# HDD.net
KiCad netlist of a schematic drawn in EAGLE
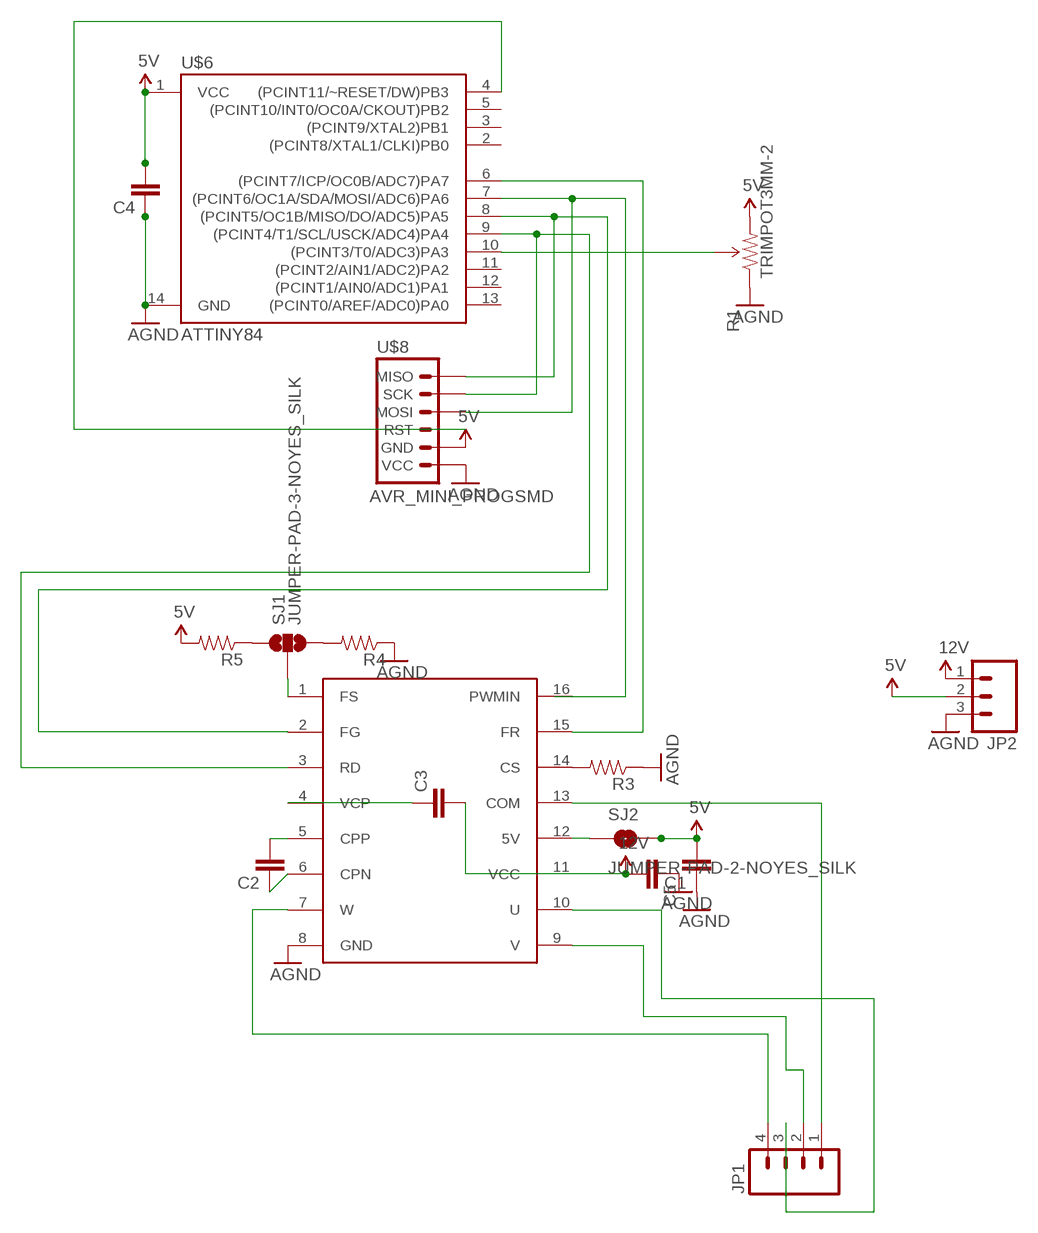
[diagram p0: schematic, sheet 1]

(export (version "E")
  (design (tool "Eeschema 10.0.6"))
  (components
    (comp (ref "C1")
      (value "CAP0805")
      (footprint "eagle-import:0805")
      (libsource (lib "eagle-import") (part "CAP0805"))
    )
    (comp (ref "C2")
      (value "CAP0805")
      (footprint "eagle-import:0805")
      (libsource (lib "eagle-import") (part "CAP0805"))
    )
    (comp (ref "C3")
      (value "CAP0805")
      (footprint "eagle-import:0805")
      (libsource (lib "eagle-import") (part "CAP0805"))
    )
    (comp (ref "C4")
      (value "CAP0805")
      (footprint "eagle-import:0805")
      (libsource (lib "eagle-import") (part "CAP0805"))
    )
    (comp (ref "C5")
      (value "CAP0805")
      (footprint "eagle-import:0805")
      (libsource (lib "eagle-import") (part "CAP0805"))
    )
    (comp (ref "JP1")
      (value "M04LOCK")
      (footprint "eagle-import:1X04_LOCK")
      (libsource (lib "eagle-import") (part "M04LOCK"))
    )
    (comp (ref "JP2")
      (value "M03PTH")
      (footprint "eagle-import:1X03")
      (libsource (lib "eagle-import") (part "M03PTH"))
    )
    (comp (ref "R1")
      (value "TRIMPOT3MM-2")
      (footprint "eagle-import:TRIMPOT-3MM-2")
      (libsource (lib "eagle-import") (part "TRIMPOT3MM-2"))
    )
    (comp (ref "R3")
      (value "RESISTOR0805-RES")
      (footprint "eagle-import:0805")
      (libsource (lib "eagle-import") (part "RESISTOR0805-RES"))
    )
    (comp (ref "R4")
      (value "RESISTOR0805-RES")
      (footprint "eagle-import:0805")
      (libsource (lib "eagle-import") (part "RESISTOR0805-RES"))
    )
    (comp (ref "R5")
      (value "RESISTOR0805-RES")
      (footprint "eagle-import:0805")
      (libsource (lib "eagle-import") (part "RESISTOR0805-RES"))
    )
    (comp (ref "SJ1")
      (value "JUMPER-PAD-3-NOYES_SILK")
      (footprint "eagle-import:PAD-JUMPER-3-NO_YES_SILK")
      (libsource (lib "eagle-import") (part "JUMPER-PAD-3-NOYES_SILK"))
    )
    (comp (ref "SJ2")
      (value "JUMPER-PAD-2-NOYES_SILK")
      (footprint "eagle-import:PAD-JUMPER-2-NO_YES_SILK")
      (libsource (lib "eagle-import") (part "JUMPER-PAD-2-NOYES_SILK"))
    )
    (comp (ref "U$1")
      (value "DRV11873")
      (footprint "eagle-import:TSSOP-16")
      (libsource (lib "eagle-import") (part "DRV11873"))
    )
    (comp (ref "U$6")
      (value "ATTINY84")
      (footprint "eagle-import:SO14")
      (libsource (lib "eagle-import") (part "ATTINY84"))
    )
    (comp (ref "U$8")
      (value "AVR_MINI_PROGSMD")
      (footprint "eagle-import:AVR_MINI_PROG")
      (libsource (lib "eagle-import") (part "AVR_MINI_PROGSMD"))
    )
  )
  (nets
    (net (code "1") (name "5V") (class "Default")
      (node (ref "C1") (pin "2") (pinfunction "2_2") (pintype "passive"))
      (node (ref "C4") (pin "2") (pinfunction "2_2") (pintype "passive"))
      (node (ref "JP2") (pin "2") (pinfunction "2_2") (pintype "passive"))
      (node (ref "R1") (pin "3") (pinfunction "CW_3") (pintype "passive"))
      (node (ref "R5") (pin "2") (pinfunction "2_2") (pintype "passive"))
      (node (ref "SJ2") (pin "2") (pinfunction "2_2") (pintype "passive"))
      (node (ref "U$6") (pin "1") (pinfunction "VCC_1") (pintype "bidirectional"))
      (node (ref "U$8") (pin "2") (pinfunction "GND_2") (pintype "passive"))
    )
    (net (code "2") (name "12V") (class "Default")
      (node (ref "C3") (pin "2") (pinfunction "2_2") (pintype "passive"))
      (node (ref "C5") (pin "2") (pinfunction "2_2") (pintype "passive"))
      (node (ref "JP2") (pin "1") (pinfunction "1_1") (pintype "passive"))
      (node (ref "U$1") (pin "11") (pinfunction "VCC_11") (pintype "bidirectional"))
    )
    (net (code "3") (name "AGND") (class "Default")
      (node (ref "C1") (pin "1") (pinfunction "1_1") (pintype "passive"))
      (node (ref "C4") (pin "1") (pinfunction "1_1") (pintype "passive"))
      (node (ref "C5") (pin "1") (pinfunction "1_1") (pintype "passive"))
      (node (ref "JP2") (pin "3") (pinfunction "3_3") (pintype "passive"))
      (node (ref "R1") (pin "1") (pinfunction "CCW_1") (pintype "passive"))
      (node (ref "R3") (pin "1") (pinfunction "1_1") (pintype "passive"))
      (node (ref "R4") (pin "1") (pinfunction "1_1") (pintype "passive"))
      (node (ref "U$1") (pin "8") (pinfunction "GND_8") (pintype "bidirectional"))
      (node (ref "U$6") (pin "14") (pinfunction "GND_14") (pintype "bidirectional"))
      (node (ref "U$8") (pin "1") (pinfunction "VCC_1") (pintype "passive"))
    )
    (net (code "4") (name "Net-(R1-WIPER)") (class "Default")
      (node (ref "R1") (pin "2") (pinfunction "WIPER_2") (pintype "passive"))
      (node (ref "U$6") (pin "10") (pinfunction "(PCINT3/T0/ADC3)PA3_10") (pintype "bidirectional"))
    )
    (net (code "5") (name "Net-(R4-Pad2)") (class "Default")
      (node (ref "R4") (pin "2") (pinfunction "2_2") (pintype "passive"))
      (node (ref "SJ1") (pin "3") (pinfunction "3_3") (pintype "passive"))
    )
    (net (code "6") (name "Net-(R5-Pad1)") (class "Default")
      (node (ref "R5") (pin "1") (pinfunction "1_1") (pintype "passive"))
      (node (ref "SJ1") (pin "1") (pinfunction "1_1") (pintype "passive"))
    )
    (net (code "7") (name "Net-(U$1-5V)") (class "Default")
      (node (ref "SJ2") (pin "1") (pinfunction "1_1") (pintype "passive"))
      (node (ref "U$1") (pin "12") (pinfunction "5V_12") (pintype "bidirectional"))
    )
    (net (code "8") (name "Net-(U$1-COM)") (class "Default")
      (node (ref "JP1") (pin "1") (pinfunction "1_1") (pintype "passive"))
      (node (ref "U$1") (pin "13") (pinfunction "COM_13") (pintype "bidirectional"))
    )
    (net (code "9") (name "Net-(U$1-CPN)") (class "Default")
      (node (ref "C2") (pin "1") (pinfunction "1_1") (pintype "passive"))
      (node (ref "U$1") (pin "6") (pinfunction "CPN_6") (pintype "bidirectional"))
    )
    (net (code "10") (name "Net-(U$1-CPP)") (class "Default")
      (node (ref "C2") (pin "2") (pinfunction "2_2") (pintype "passive"))
      (node (ref "U$1") (pin "5") (pinfunction "CPP_5") (pintype "bidirectional"))
    )
    (net (code "11") (name "Net-(U$1-CS)") (class "Default")
      (node (ref "R3") (pin "2") (pinfunction "2_2") (pintype "passive"))
      (node (ref "U$1") (pin "14") (pinfunction "CS_14") (pintype "bidirectional"))
    )
    (net (code "12") (name "Net-(U$1-FG)") (class "Default")
      (node (ref "U$1") (pin "2") (pinfunction "FG_2") (pintype "bidirectional"))
      (node (ref "U$6") (pin "8") (pinfunction "(PCINT5/OC1B/MISO/DO/ADC5)PA5_8") (pintype "bidirectional"))
      (node (ref "U$8") (pin "6") (pinfunction "MISO_6") (pintype "passive"))
    )
    (net (code "13") (name "Net-(U$1-FR)") (class "Default")
      (node (ref "U$1") (pin "15") (pinfunction "FR_15") (pintype "bidirectional"))
      (node (ref "U$6") (pin "6") (pinfunction "(PCINT7/ICP/OC0B/ADC7)PA7_6") (pintype "bidirectional"))
    )
    (net (code "14") (name "Net-(U$1-FS)") (class "Default")
      (node (ref "SJ1") (pin "2") (pinfunction "2_2") (pintype "passive"))
      (node (ref "U$1") (pin "1") (pinfunction "FS_1") (pintype "bidirectional"))
    )
    (net (code "15") (name "Net-(U$1-RD)") (class "Default")
      (node (ref "U$1") (pin "3") (pinfunction "RD_3") (pintype "bidirectional"))
      (node (ref "U$6") (pin "9") (pinfunction "(PCINT4/T1/SCL/USCK/ADC4)PA4_9") (pintype "bidirectional"))
      (node (ref "U$8") (pin "5") (pinfunction "SCK_5") (pintype "passive"))
    )
    (net (code "16") (name "Net-(U$1-U)") (class "Default")
      (node (ref "JP1") (pin "3") (pinfunction "3_3") (pintype "passive"))
      (node (ref "U$1") (pin "10") (pinfunction "U_10") (pintype "bidirectional"))
    )
    (net (code "17") (name "Net-(U$1-V)") (class "Default")
      (node (ref "JP1") (pin "2") (pinfunction "2_2") (pintype "passive"))
      (node (ref "U$1") (pin "9") (pinfunction "V_9") (pintype "bidirectional"))
    )
    (net (code "18") (name "Net-(U$1-VCP)") (class "Default")
      (node (ref "C3") (pin "1") (pinfunction "1_1") (pintype "passive"))
      (node (ref "U$1") (pin "4") (pinfunction "VCP_4") (pintype "bidirectional"))
    )
    (net (code "19") (name "Net-(U$1-W)") (class "Default")
      (node (ref "JP1") (pin "4") (pinfunction "4_4") (pintype "passive"))
      (node (ref "U$1") (pin "7") (pinfunction "W_7") (pintype "bidirectional"))
    )
    (net (code "20") (name "Net-(U$6-(PCINT6{slash}OC1A{slash}SDA{slash}MOSI{slash}ADC6)PA6)") (class "Default")
      (node (ref "U$6") (pin "7") (pinfunction "(PCINT6/OC1A/SDA/MOSI/ADC6)PA6_7") (pintype "bidirectional"))
      (node (ref "U$8") (pin "4") (pinfunction "MOSI_4") (pintype "passive"))
    )
    (net (code "21") (name "Net-(U$6-(PCINT11{slash}~{RESET{slash}DW})PB3)") (class "Default")
      (node (ref "U$6") (pin "4") (pinfunction "(PCINT11/~{RESET/DW})PB3_4") (pintype "bidirectional"))
      (node (ref "U$8") (pin "3") (pinfunction "RST_3") (pintype "passive"))
    )
    (net (code "22") (name "unconnected-(U$1-PWMIN-Pad16)") (class "Default")
      (node (ref "U$1") (pin "16") (pinfunction "PWMIN_16") (pintype "bidirectional"))
    )
    (net (code "23") (name "unconnected-(U$6-(PCINT0{slash}AREF{slash}ADC0)PA0-Pad13)") (class "Default")
      (node (ref "U$6") (pin "13") (pinfunction "(PCINT0/AREF/ADC0)PA0_13") (pintype "bidirectional"))
    )
    (net (code "24") (name "unconnected-(U$6-(PCINT1{slash}AIN0{slash}ADC1)PA1-Pad12)") (class "Default")
      (node (ref "U$6") (pin "12") (pinfunction "(PCINT1/AIN0/ADC1)PA1_12") (pintype "bidirectional"))
    )
    (net (code "25") (name "unconnected-(U$6-(PCINT2{slash}AIN1{slash}ADC2)PA2-Pad11)") (class "Default")
      (node (ref "U$6") (pin "11") (pinfunction "(PCINT2/AIN1/ADC2)PA2_11") (pintype "bidirectional"))
    )
    (net (code "26") (name "unconnected-(U$6-(PCINT8{slash}XTAL1{slash}CLKI)PB0-Pad2)") (class "Default")
      (node (ref "U$6") (pin "2") (pinfunction "(PCINT8/XTAL1/CLKI)PB0_2") (pintype "bidirectional"))
    )
    (net (code "27") (name "unconnected-(U$6-(PCINT9{slash}XTAL2)PB1-Pad3)") (class "Default")
      (node (ref "U$6") (pin "3") (pinfunction "(PCINT9/XTAL2)PB1_3") (pintype "bidirectional"))
    )
    (net (code "28") (name "unconnected-(U$6-(PCINT10{slash}INT0{slash}OC0A{slash}CKOUT)PB2-Pad5)") (class "Default")
      (node (ref "U$6") (pin "5") (pinfunction "(PCINT10/INT0/OC0A/CKOUT)PB2_5") (pintype "bidirectional"))
    )
  )
)
